# watch_game.net
KiCad netlist of a schematic drawn in EAGLE
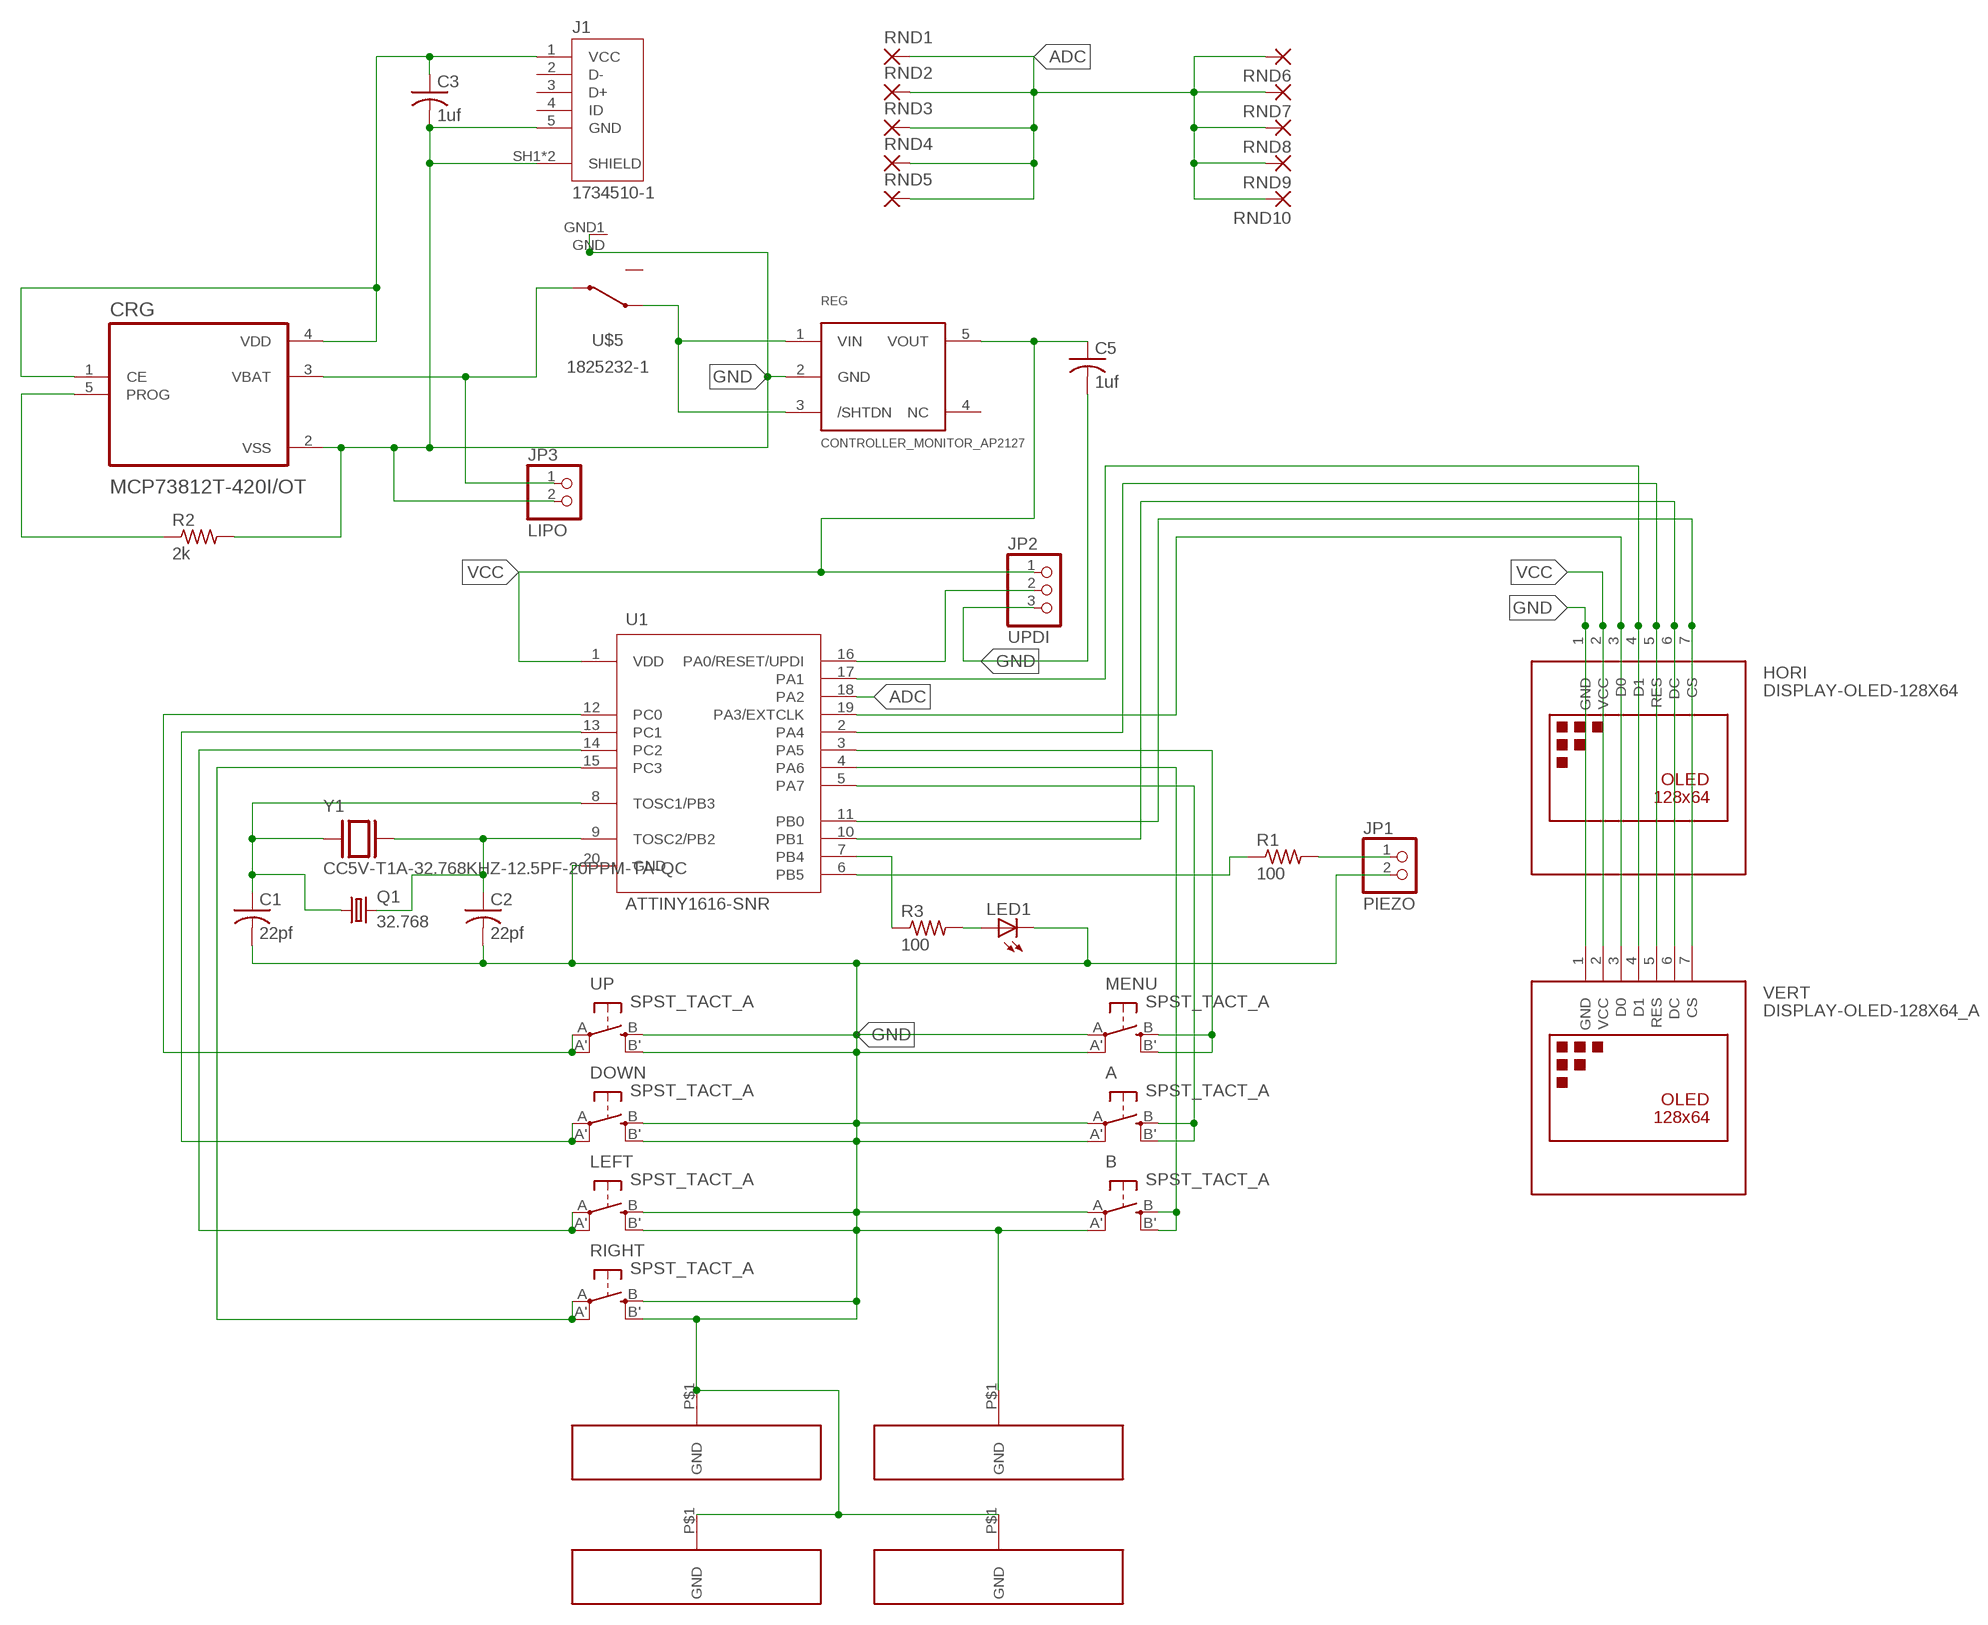
[diagram p0: schematic, sheet 1]

(export (version "E")
  (design (tool "Eeschema 10.0.6"))
  (components
    (comp (ref "A")
      (value "SPST_TACT_A")
      (footprint "eagle-import:EVQ-Q2_A")
      (libsource (lib "eagle-import") (part "SPST_TACT_A"))
    )
    (comp (ref "B")
      (value "SPST_TACT_A")
      (footprint "eagle-import:EVQ-Q2_A")
      (libsource (lib "eagle-import") (part "SPST_TACT_A"))
    )
    (comp (ref "C1")
      (value "22pf")
      (footprint "eagle-import:C0805")
      (libsource (lib "eagle-import") (part "C-USC0805"))
    )
    (comp (ref "C2")
      (value "22pf")
      (footprint "eagle-import:C0805")
      (libsource (lib "eagle-import") (part "C-USC0805"))
    )
    (comp (ref "C3")
      (value "1uf")
      (footprint "eagle-import:C0805")
      (libsource (lib "eagle-import") (part "rcl_334_C-USC0805"))
    )
    (comp (ref "C5")
      (value "1uf")
      (footprint "eagle-import:C0805")
      (libsource (lib "eagle-import") (part "rcl_334_C-USC0805"))
    )
    (comp (ref "CRG")
      (value "MCP73812T-420I/OT")
      (footprint "eagle-import:SOT95P280X145-5N")
      (fields (field (name "MF") "Microchip"))
      (libsource (lib "eagle-import") (part "MCP73812T-420I/OT"))
    )
    (comp (ref "DOWN")
      (value "SPST_TACT_A")
      (footprint "eagle-import:EVQ-Q2_A")
      (libsource (lib "eagle-import") (part "SPST_TACT_A"))
    )
    (comp (ref "HORI")
      (value "DISPLAY-OLED-128X64")
      (footprint "eagle-import:DISPLAY-OLED-128X64")
      (libsource (lib "eagle-import") (part "DISPLAY-OLED-128X64"))
    )
    (comp (ref "J1")
      (value "1734510-1")
      (footprint "eagle-import:TE_1734510-1")
      (fields (field (name "MF") "TE Connectivity"))
      (libsource (lib "eagle-import") (part "1734510-1"))
    )
    (comp (ref "JP1")
      (value "PIEZO")
      (footprint "eagle-import:1X02")
      (libsource (lib "eagle-import") (part "PINHD-1X2"))
    )
    (comp (ref "JP2")
      (value "UPDI")
      (footprint "eagle-import:1X03")
      (libsource (lib "eagle-import") (part "PINHD-1X3"))
    )
    (comp (ref "JP3")
      (value "LIPO")
      (footprint "eagle-import:1X02")
      (libsource (lib "eagle-import") (part "PINHD-1X2"))
    )
    (comp (ref "LED1")
      (value "LED5MM")
      (footprint "eagle-import:LED5MM")
      (libsource (lib "eagle-import") (part "LED5MM"))
    )
    (comp (ref "LEFT")
      (value "SPST_TACT_A")
      (footprint "eagle-import:EVQ-Q2_A")
      (libsource (lib "eagle-import") (part "SPST_TACT_A"))
    )
    (comp (ref "MENU")
      (value "SPST_TACT_A")
      (footprint "eagle-import:EVQ-Q2_A")
      (libsource (lib "eagle-import") (part "SPST_TACT_A"))
    )
    (comp (ref "Q1")
      (value "32.768")
      (footprint "eagle-import:TC26H")
      (libsource (lib "eagle-import") (part "CRYSTALTC26H"))
    )
    (comp (ref "R1")
      (value "100")
      (footprint "eagle-import:M0805")
      (libsource (lib "eagle-import") (part "R-US_M0805"))
    )
    (comp (ref "R2")
      (value "2k")
      (footprint "eagle-import:M0805")
      (libsource (lib "eagle-import") (part "R-US_M0805"))
    )
    (comp (ref "R3")
      (value "100")
      (footprint "eagle-import:M0805")
      (libsource (lib "eagle-import") (part "R-US_M0805"))
    )
    (comp (ref "REG")
      (value "CONTROLLER_MONITOR_AP2127")
      (footprint "eagle-import:CONTROLLER_MONITOR_SOT23-5")
      (libsource (lib "eagle-import") (part "CONTROLLER_MONITOR_AP2127"))
    )
    (comp (ref "RIGHT")
      (value "SPST_TACT_A")
      (footprint "eagle-import:EVQ-Q2_A")
      (libsource (lib "eagle-import") (part "SPST_TACT_A"))
    )
    (comp (ref "RND1")
      (value "SMD5")
      (footprint "eagle-import:SMD2,54-5,08")
      (libsource (lib "eagle-import") (part "SMD5"))
    )
    (comp (ref "RND2")
      (value "SMD5")
      (footprint "eagle-import:SMD2,54-5,08")
      (libsource (lib "eagle-import") (part "SMD5"))
    )
    (comp (ref "RND3")
      (value "SMD5")
      (footprint "eagle-import:SMD2,54-5,08")
      (libsource (lib "eagle-import") (part "SMD5"))
    )
    (comp (ref "RND4")
      (value "SMD5")
      (footprint "eagle-import:SMD2,54-5,08")
      (libsource (lib "eagle-import") (part "SMD5"))
    )
    (comp (ref "RND5")
      (value "SMD5")
      (footprint "eagle-import:SMD2,54-5,08")
      (libsource (lib "eagle-import") (part "SMD5"))
    )
    (comp (ref "RND6")
      (value "SMD5")
      (footprint "eagle-import:SMD2,54-5,08")
      (libsource (lib "eagle-import") (part "SMD5"))
    )
    (comp (ref "RND7")
      (value "SMD5")
      (footprint "eagle-import:SMD2,54-5,08")
      (libsource (lib "eagle-import") (part "SMD5"))
    )
    (comp (ref "RND8")
      (value "SMD5")
      (footprint "eagle-import:SMD2,54-5,08")
      (libsource (lib "eagle-import") (part "SMD5"))
    )
    (comp (ref "RND9")
      (value "SMD5")
      (footprint "eagle-import:SMD2,54-5,08")
      (libsource (lib "eagle-import") (part "SMD5"))
    )
    (comp (ref "RND10")
      (value "SMD5")
      (footprint "eagle-import:SMD2,54-5,08")
      (libsource (lib "eagle-import") (part "SMD5"))
    )
    (comp (ref "U$5")
      (value "1825232-1")
      (footprint "eagle-import:1825232-1")
      (fields (field (name "MF") "TE Connectivity"))
      (libsource (lib "eagle-import") (part "1825232-1"))
    )
    (comp (ref "U$6")
      (value "GND_STRIP_600MIL")
      (footprint "eagle-import:GND_PADS_2")
      (libsource (lib "eagle-import") (part "GND_STRIP_600MIL"))
    )
    (comp (ref "U$7")
      (value "GND_STRIP_600MIL")
      (footprint "eagle-import:GND_PADS_2")
      (libsource (lib "eagle-import") (part "GND_STRIP_600MIL"))
    )
    (comp (ref "U$8")
      (value "GND_STRIP_600MIL")
      (footprint "eagle-import:GND_PADS_2")
      (libsource (lib "eagle-import") (part "GND_STRIP_600MIL"))
    )
    (comp (ref "U$9")
      (value "GND_STRIP_600MIL")
      (footprint "eagle-import:GND_PADS_2")
      (libsource (lib "eagle-import") (part "GND_STRIP_600MIL"))
    )
    (comp (ref "U1")
      (value "ATTINY1616-SNR")
      (footprint "eagle-import:SOIC127P1032X265-20N")
      (fields (field (name "MF") "Microchip"))
      (libsource (lib "eagle-import") (part "ATTINY1616-SNR"))
    )
    (comp (ref "UP")
      (value "SPST_TACT_A")
      (footprint "eagle-import:EVQ-Q2_A")
      (libsource (lib "eagle-import") (part "SPST_TACT_A"))
    )
    (comp (ref "VERT")
      (value "DISPLAY-OLED-128X64_A")
      (footprint "eagle-import:DISPLAY-OLED-128X64_A")
      (libsource (lib "eagle-import") (part "DISPLAY-OLED-128X64_A"))
    )
    (comp (ref "Y1")
      (value "CC5V-T1A-32.768KHZ-12.5PF-20PPM-TA-QC")
      (footprint "eagle-import:XTAL_CC5V-T1A-32.768KHZ-12.5PF-20PPM-TA-QC")
      (fields (field (name "MF") "Micro Crystal") (field (name "MP") "CC5V-T1A-32.768kHz-12.5pF-20PPM-TA-QC"))
      (libsource (lib "eagle-import") (part "CC5V-T1A-32.768KHZ-12.5PF-20PPM-TA-QC"))
    )
  )
  (nets
    (net (code "1") (name "ADC") (class "Default")
      (node (ref "RND1") (pin "1") (pinfunction "P_1") (pintype "passive"))
      (node (ref "RND10") (pin "1") (pinfunction "P_1") (pintype "passive"))
      (node (ref "RND2") (pin "1") (pinfunction "P_1") (pintype "passive"))
      (node (ref "RND3") (pin "1") (pinfunction "P_1") (pintype "passive"))
      (node (ref "RND4") (pin "1") (pinfunction "P_1") (pintype "passive"))
      (node (ref "RND5") (pin "1") (pinfunction "P_1") (pintype "passive"))
      (node (ref "RND6") (pin "1") (pinfunction "P_1") (pintype "passive"))
      (node (ref "RND7") (pin "1") (pinfunction "P_1") (pintype "passive"))
      (node (ref "RND8") (pin "1") (pinfunction "P_1") (pintype "passive"))
      (node (ref "RND9") (pin "1") (pinfunction "P_1") (pintype "passive"))
      (node (ref "U1") (pin "18") (pinfunction "PA2_18") (pintype "bidirectional"))
    )
    (net (code "2") (name "GND") (class "Default")
      (node (ref "A") (pin "A") (pinfunction "P_A") (pintype "passive"))
      (node (ref "A") (pin "A'") (pinfunction "P1_A'") (pintype "passive"))
      (node (ref "B") (pin "A") (pinfunction "P_A") (pintype "passive"))
      (node (ref "B") (pin "A'") (pinfunction "P1_A'") (pintype "passive"))
      (node (ref "C1") (pin "2") (pinfunction "2_2") (pintype "passive"))
      (node (ref "C2") (pin "2") (pinfunction "2_2") (pintype "passive"))
      (node (ref "C3") (pin "2") (pinfunction "2_2") (pintype "passive"))
      (node (ref "C5") (pin "2") (pinfunction "2_2") (pintype "passive"))
      (node (ref "CRG") (pin "2") (pinfunction "VSS_2") (pintype "power_in"))
      (node (ref "DOWN") (pin "B") (pinfunction "S_B") (pintype "passive"))
      (node (ref "DOWN") (pin "B'") (pinfunction "S1_B'") (pintype "passive"))
      (node (ref "HORI") (pin "1") (pinfunction "GND_1") (pintype "power_in"))
      (node (ref "J1") (pin "5") (pinfunction "GND_5") (pintype "passive"))
      (node (ref "J1") (pin "SH1") (pinfunction "SHIELD_SH1") (pintype "passive"))
      (node (ref "J1") (pin "SH2") (pinfunction "SHIELD_SH2") (pintype "passive"))
      (node (ref "JP1") (pin "2") (pinfunction "2_2") (pintype "passive"))
      (node (ref "JP2") (pin "3") (pinfunction "3_3") (pintype "passive"))
      (node (ref "JP3") (pin "2") (pinfunction "2_2") (pintype "passive"))
      (node (ref "LED1") (pin "K") (pinfunction "C_K") (pintype "passive"))
      (node (ref "LEFT") (pin "B") (pinfunction "S_B") (pintype "passive"))
      (node (ref "LEFT") (pin "B'") (pinfunction "S1_B'") (pintype "passive"))
      (node (ref "MENU") (pin "A") (pinfunction "P_A") (pintype "passive"))
      (node (ref "MENU") (pin "A'") (pinfunction "P1_A'") (pintype "passive"))
      (node (ref "R2") (pin "2") (pinfunction "2_2") (pintype "passive"))
      (node (ref "REG") (pin "2") (pinfunction "GND_2") (pintype "bidirectional"))
      (node (ref "RIGHT") (pin "B") (pinfunction "S_B") (pintype "passive"))
      (node (ref "RIGHT") (pin "B'") (pinfunction "S1_B'") (pintype "passive"))
      (node (ref "U$5") (pin "GND") (pinfunction "GND_GND") (pintype "passive"))
      (node (ref "U$5") (pin "GND1") (pinfunction "GND1_GND1") (pintype "passive"))
      (node (ref "U$6") (pin "P$1") (pinfunction "GND_P$1") (pintype "bidirectional"))
      (node (ref "U$7") (pin "P$1") (pinfunction "GND_P$1") (pintype "bidirectional"))
      (node (ref "U$8") (pin "P$1") (pinfunction "GND_P$1") (pintype "bidirectional"))
      (node (ref "U$9") (pin "P$1") (pinfunction "GND_P$1") (pintype "bidirectional"))
      (node (ref "U1") (pin "20") (pinfunction "GND_20") (pintype "power_in"))
      (node (ref "UP") (pin "B") (pinfunction "S_B") (pintype "passive"))
      (node (ref "UP") (pin "B'") (pinfunction "S1_B'") (pintype "passive"))
      (node (ref "VERT") (pin "1") (pinfunction "GND_1") (pintype "power_in"))
    )
    (net (code "3") (name "Net-(A-S)") (class "Default")
      (node (ref "A") (pin "B") (pinfunction "S_B") (pintype "passive"))
      (node (ref "A") (pin "B'") (pinfunction "S1_B'") (pintype "passive"))
      (node (ref "U1") (pin "5") (pinfunction "PA7_5") (pintype "bidirectional"))
    )
    (net (code "4") (name "Net-(B-S)") (class "Default")
      (node (ref "B") (pin "B") (pinfunction "S_B") (pintype "passive"))
      (node (ref "B") (pin "B'") (pinfunction "S1_B'") (pintype "passive"))
      (node (ref "U1") (pin "4") (pinfunction "PA6_4") (pintype "bidirectional"))
    )
    (net (code "5") (name "Net-(CRG-CE)") (class "Default")
      (node (ref "C3") (pin "1") (pinfunction "1_1") (pintype "passive"))
      (node (ref "CRG") (pin "1") (pinfunction "CE_1") (pintype "input"))
      (node (ref "CRG") (pin "4") (pinfunction "VDD_4") (pintype "power_in"))
      (node (ref "J1") (pin "1") (pinfunction "VCC_1") (pintype "passive"))
    )
    (net (code "6") (name "Net-(CRG-PROG)") (class "Default")
      (node (ref "CRG") (pin "5") (pinfunction "PROG_5") (pintype "input"))
      (node (ref "R2") (pin "1") (pinfunction "1_1") (pintype "passive"))
    )
    (net (code "7") (name "Net-(CRG-VBAT)") (class "Default")
      (node (ref "CRG") (pin "3") (pinfunction "VBAT_3") (pintype "output"))
      (node (ref "JP3") (pin "1") (pinfunction "1_1") (pintype "passive"))
      (node (ref "U$5") (pin "2") (pinfunction "2_2") (pintype "passive"))
    )
    (net (code "8") (name "Net-(DOWN-P)") (class "Default")
      (node (ref "DOWN") (pin "A") (pinfunction "P_A") (pintype "passive"))
      (node (ref "DOWN") (pin "A'") (pinfunction "P1_A'") (pintype "passive"))
      (node (ref "U1") (pin "13") (pinfunction "PC1_13") (pintype "bidirectional"))
    )
    (net (code "9") (name "Net-(HORI-CS)") (class "Default")
      (node (ref "HORI") (pin "7") (pinfunction "CS_7") (pintype "bidirectional"))
      (node (ref "U1") (pin "11") (pinfunction "PB0_11") (pintype "bidirectional"))
      (node (ref "VERT") (pin "7") (pinfunction "CS_7") (pintype "bidirectional"))
    )
    (net (code "10") (name "Net-(HORI-D0)") (class "Default")
      (node (ref "HORI") (pin "3") (pinfunction "D0_3") (pintype "bidirectional"))
      (node (ref "U1") (pin "19") (pinfunction "PA3/EXTCLK_19") (pintype "bidirectional"))
      (node (ref "VERT") (pin "3") (pinfunction "D0_3") (pintype "bidirectional"))
    )
    (net (code "11") (name "Net-(HORI-D1)") (class "Default")
      (node (ref "HORI") (pin "4") (pinfunction "D1_4") (pintype "bidirectional"))
      (node (ref "U1") (pin "17") (pinfunction "PA1_17") (pintype "bidirectional"))
      (node (ref "VERT") (pin "4") (pinfunction "D1_4") (pintype "bidirectional"))
    )
    (net (code "12") (name "Net-(HORI-DC)") (class "Default")
      (node (ref "HORI") (pin "6") (pinfunction "DC_6") (pintype "bidirectional"))
      (node (ref "U1") (pin "10") (pinfunction "PB1_10") (pintype "bidirectional"))
      (node (ref "VERT") (pin "6") (pinfunction "DC_6") (pintype "bidirectional"))
    )
    (net (code "13") (name "Net-(HORI-RES)") (class "Default")
      (node (ref "HORI") (pin "5") (pinfunction "RES_5") (pintype "bidirectional"))
      (node (ref "U1") (pin "2") (pinfunction "PA4_2") (pintype "bidirectional"))
      (node (ref "VERT") (pin "5") (pinfunction "RES_5") (pintype "bidirectional"))
    )
    (net (code "14") (name "Net-(JP1-Pad1)") (class "Default")
      (node (ref "JP1") (pin "1") (pinfunction "1_1") (pintype "passive"))
      (node (ref "R1") (pin "2") (pinfunction "2_2") (pintype "passive"))
    )
    (net (code "15") (name "Net-(LED1-PadA)") (class "Default")
      (node (ref "LED1") (pin "A") (pinfunction "A_A") (pintype "passive"))
      (node (ref "R3") (pin "2") (pinfunction "2_2") (pintype "passive"))
    )
    (net (code "16") (name "Net-(LEFT-P)") (class "Default")
      (node (ref "LEFT") (pin "A") (pinfunction "P_A") (pintype "passive"))
      (node (ref "LEFT") (pin "A'") (pinfunction "P1_A'") (pintype "passive"))
      (node (ref "U1") (pin "14") (pinfunction "PC2_14") (pintype "bidirectional"))
    )
    (net (code "17") (name "Net-(MENU-S)") (class "Default")
      (node (ref "MENU") (pin "B") (pinfunction "S_B") (pintype "passive"))
      (node (ref "MENU") (pin "B'") (pinfunction "S1_B'") (pintype "passive"))
      (node (ref "U1") (pin "3") (pinfunction "PA5_3") (pintype "bidirectional"))
    )
    (net (code "18") (name "Net-(REG-VIN)") (class "Default")
      (node (ref "REG") (pin "1") (pinfunction "VIN_1") (pintype "bidirectional"))
      (node (ref "REG") (pin "3") (pinfunction "/SHTDN_3") (pintype "bidirectional"))
      (node (ref "U$5") (pin "3") (pinfunction "3_3") (pintype "passive"))
    )
    (net (code "19") (name "Net-(RIGHT-P)") (class "Default")
      (node (ref "RIGHT") (pin "A") (pinfunction "P_A") (pintype "passive"))
      (node (ref "RIGHT") (pin "A'") (pinfunction "P1_A'") (pintype "passive"))
      (node (ref "U1") (pin "15") (pinfunction "PC3_15") (pintype "bidirectional"))
    )
    (net (code "20") (name "Net-(U1-PA0{slash}RESET{slash}UPDI)") (class "Default")
      (node (ref "JP2") (pin "2") (pinfunction "2_2") (pintype "passive"))
      (node (ref "U1") (pin "16") (pinfunction "PA0/RESET/UPDI_16") (pintype "bidirectional"))
    )
    (net (code "21") (name "Net-(U1-PB4)") (class "Default")
      (node (ref "R3") (pin "1") (pinfunction "1_1") (pintype "passive"))
      (node (ref "U1") (pin "7") (pinfunction "PB4_7") (pintype "bidirectional"))
    )
    (net (code "22") (name "Net-(U1-PB5)") (class "Default")
      (node (ref "R1") (pin "1") (pinfunction "1_1") (pintype "passive"))
      (node (ref "U1") (pin "6") (pinfunction "PB5_6") (pintype "bidirectional"))
    )
    (net (code "23") (name "Net-(U1-PC0)") (class "Default")
      (node (ref "U1") (pin "12") (pinfunction "PC0_12") (pintype "bidirectional"))
      (node (ref "UP") (pin "A") (pinfunction "P_A") (pintype "passive"))
      (node (ref "UP") (pin "A'") (pinfunction "P1_A'") (pintype "passive"))
    )
    (net (code "24") (name "Net-(U1-TOSC1{slash}PB3)") (class "Default")
      (node (ref "C1") (pin "1") (pinfunction "1_1") (pintype "passive"))
      (node (ref "Q1") (pin "1") (pinfunction "1_1") (pintype "passive"))
      (node (ref "U1") (pin "8") (pinfunction "TOSC1/PB3_8") (pintype "bidirectional"))
      (node (ref "Y1") (pin "1") (pinfunction "1_1") (pintype "passive"))
    )
    (net (code "25") (name "Net-(U1-TOSC2{slash}PB2)") (class "Default")
      (node (ref "C2") (pin "1") (pinfunction "1_1") (pintype "passive"))
      (node (ref "Q1") (pin "2") (pinfunction "2_2") (pintype "passive"))
      (node (ref "U1") (pin "9") (pinfunction "TOSC2/PB2_9") (pintype "bidirectional"))
      (node (ref "Y1") (pin "2") (pinfunction "2_2") (pintype "passive"))
    )
    (net (code "26") (name "VCC") (class "Default")
      (node (ref "C5") (pin "1") (pinfunction "1_1") (pintype "passive"))
      (node (ref "HORI") (pin "2") (pinfunction "VCC_2") (pintype "power_in"))
      (node (ref "JP2") (pin "1") (pinfunction "1_1") (pintype "passive"))
      (node (ref "REG") (pin "5") (pinfunction "VOUT_5") (pintype "bidirectional"))
      (node (ref "U1") (pin "1") (pinfunction "VDD_1") (pintype "power_in"))
      (node (ref "VERT") (pin "2") (pinfunction "VCC_2") (pintype "power_in"))
    )
    (net (code "27") (name "unconnected-(J1-D+-Pad3)") (class "Default")
      (node (ref "J1") (pin "3") (pinfunction "D+_3") (pintype "passive"))
    )
    (net (code "28") (name "unconnected-(J1-D--Pad2)") (class "Default")
      (node (ref "J1") (pin "2") (pinfunction "D-_2") (pintype "passive"))
    )
    (net (code "29") (name "unconnected-(J1-ID-Pad4)") (class "Default")
      (node (ref "J1") (pin "4") (pinfunction "ID_4") (pintype "passive"))
    )
    (net (code "30") (name "unconnected-(REG-NC-Pad4)") (class "Default")
      (node (ref "REG") (pin "4") (pinfunction "NC_4") (pintype "bidirectional"))
    )
    (net (code "31") (name "unconnected-(U$5-Pad1)") (class "Default")
      (node (ref "U$5") (pin "1") (pinfunction "1_1") (pintype "passive"))
    )
  )
)
